# rapidshark-nmos-quarter-bridge-mk-1_0.net
KiCad netlist of a schematic drawn in EAGLE
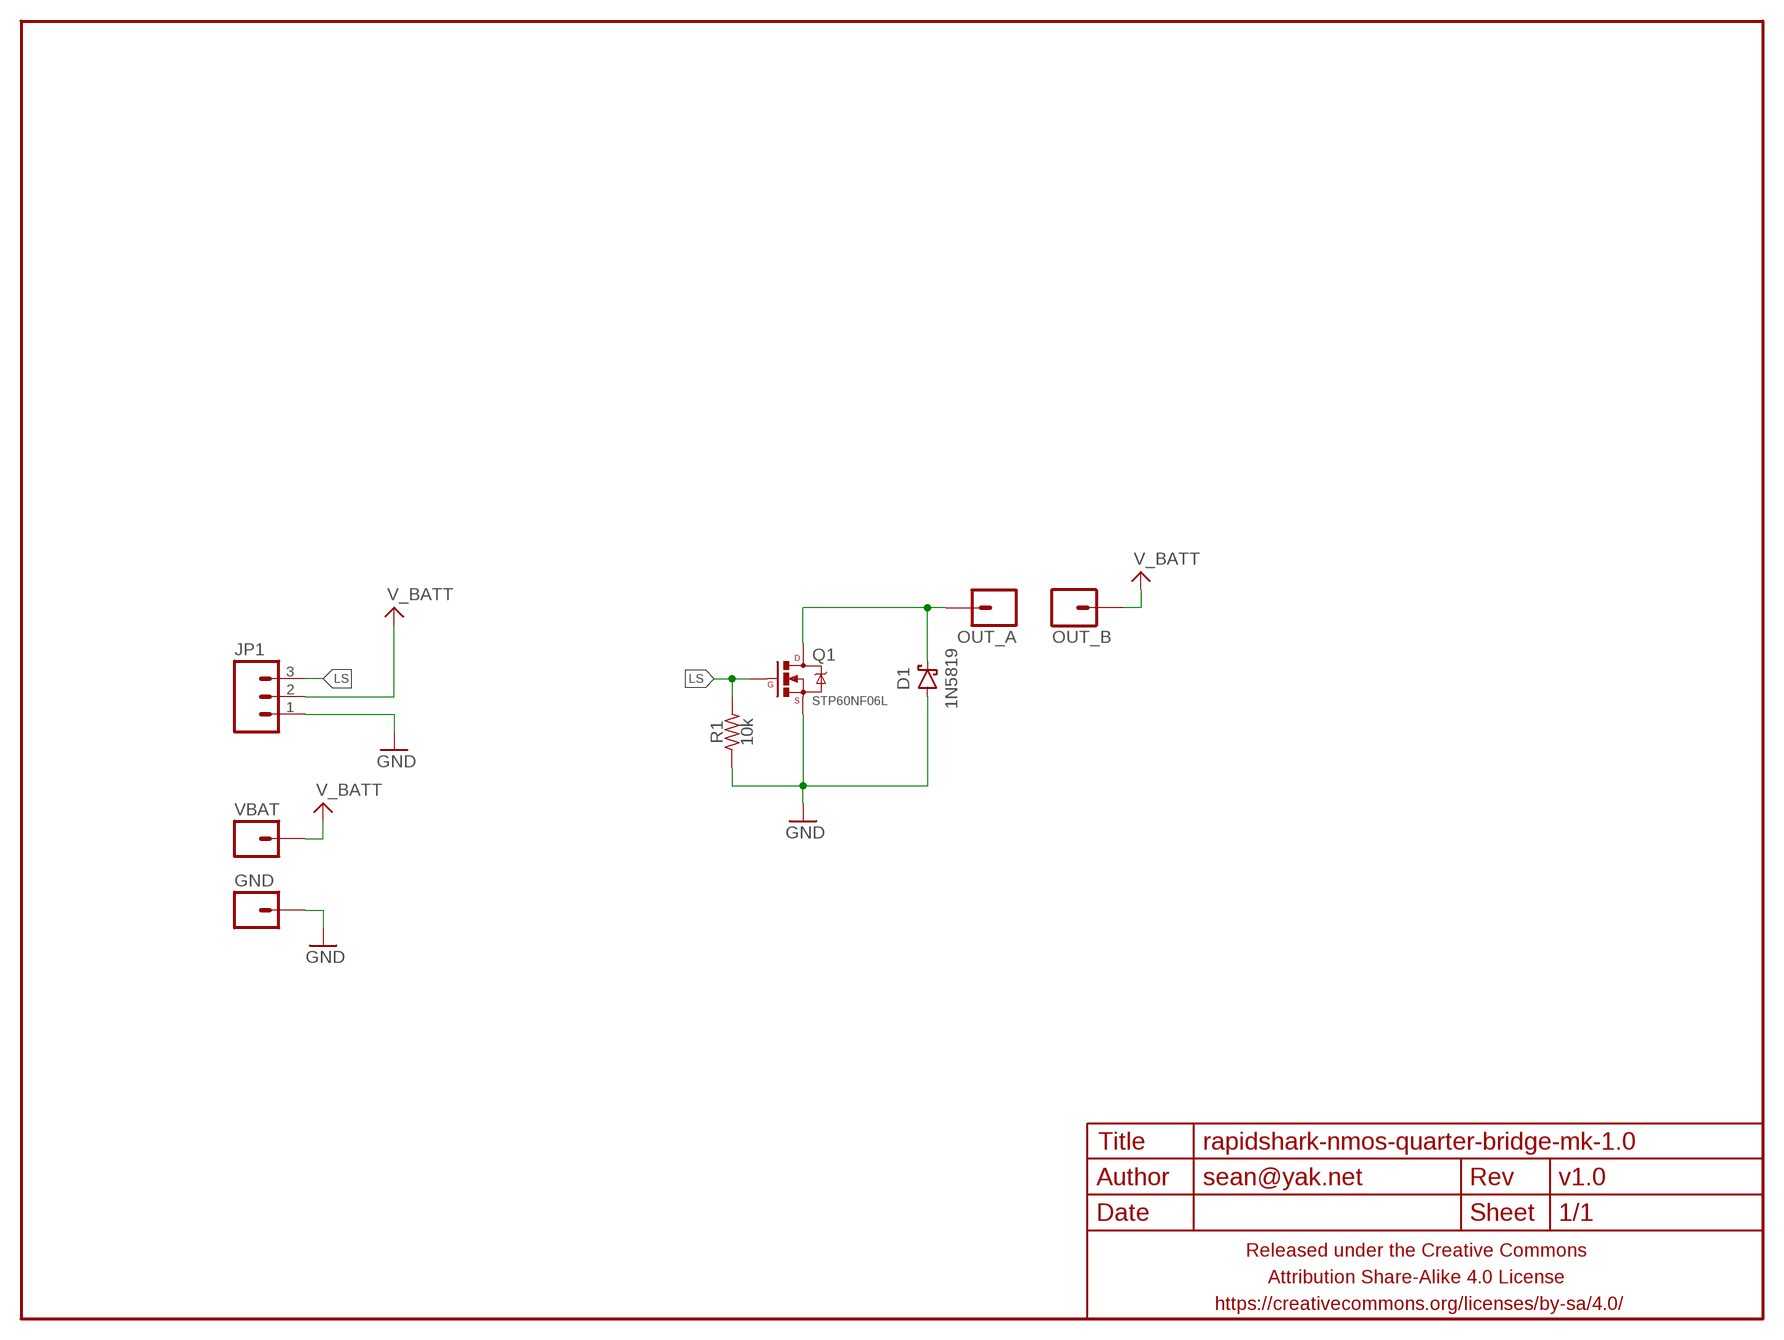
[diagram p0: schematic, sheet 1]

(export (version "E")
  (design (tool "Eeschema 10.0.6"))
  (components
    (comp (ref "D1")
      (value "1N5819")
      (footprint "eagle-import:DIODE-SCHOTTKY-10.16MM")
      (libsource (lib "eagle-import") (part "DIODE-SCHOTTKYPTH-10.16MM"))
    )
    (comp (ref "FRAME1")
      (value "FRAME-LETTERNO_PACKAGE")
      (footprint "eagle-import:DUMMY")
      (fields (field (name "DESIGNER") "sean@yak.net") (field (name "VERSION") "v1.0"))
      (libsource (lib "eagle-import") (part "FRAME-LETTERNO_PACKAGE"))
    )
    (comp (ref "GND")
      (value "M0112AWG")
      (footprint "eagle-import:1X01-12AWG")
      (libsource (lib "eagle-import") (part "M0112AWG"))
    )
    (comp (ref "JP1")
      (value "M03PTH-CENTERED")
      (footprint "eagle-import:1X03-CENTERED")
      (libsource (lib "eagle-import") (part "M03PTH-CENTERED"))
    )
    (comp (ref "OUT_A")
      (value "M0112AWG")
      (footprint "eagle-import:1X01-12AWG")
      (libsource (lib "eagle-import") (part "M0112AWG"))
    )
    (comp (ref "OUT_B")
      (value "M0112AWG")
      (footprint "eagle-import:1X01-12AWG")
      (libsource (lib "eagle-import") (part "M0112AWG"))
    )
    (comp (ref "Q1")
      (value "STP60NF06L")
      (footprint "eagle-import:TO220-THERMPAD")
      (libsource (lib "eagle-import") (part "MOSFET-NCHANNELTO-220"))
    )
    (comp (ref "R1")
      (value "10k")
      (footprint "eagle-import:RESISTOR-AXIAL-PTH-5.08MM")
      (libsource (lib "eagle-import") (part "RESISTORPTH-AXIAL-5.08MM"))
    )
    (comp (ref "VBAT")
      (value "M0112AWG")
      (footprint "eagle-import:1X01-12AWG")
      (libsource (lib "eagle-import") (part "M0112AWG"))
    )
  )
  (nets
    (net (code "1") (name "GND") (class "Default")
      (node (ref "D1") (pin "A") (pinfunction "A_A") (pintype "passive"))
      (node (ref "GND") (pin "1") (pinfunction "1_1") (pintype "passive"))
      (node (ref "JP1") (pin "1") (pinfunction "1_1") (pintype "passive"))
      (node (ref "Q1") (pin "3") (pinfunction "S_3") (pintype "passive"))
      (node (ref "R1") (pin "P$1") (pinfunction "1_P$1") (pintype "passive"))
    )
    (net (code "2") (name "LS") (class "Default")
      (node (ref "JP1") (pin "3") (pinfunction "3_3") (pintype "passive"))
      (node (ref "Q1") (pin "1") (pinfunction "G_1") (pintype "passive"))
      (node (ref "R1") (pin "P$2") (pinfunction "2_P$2") (pintype "passive"))
    )
    (net (code "3") (name "Net-(D1-PadC)") (class "Default")
      (node (ref "D1") (pin "C") (pinfunction "C_C") (pintype "passive"))
      (node (ref "OUT_A") (pin "1") (pinfunction "1_1") (pintype "passive"))
      (node (ref "Q1") (pin "2@1") (pinfunction "D_2@1") (pintype "passive"))
      (node (ref "Q1") (pin "2@2") (pinfunction "D_2@2") (pintype "passive"))
    )
    (net (code "4") (name "V_BATT") (class "Default")
      (node (ref "JP1") (pin "2") (pinfunction "2_2") (pintype "passive"))
      (node (ref "OUT_B") (pin "1") (pinfunction "1_1") (pintype "passive"))
      (node (ref "VBAT") (pin "1") (pinfunction "1_1") (pintype "passive"))
    )
  )
)
